# MCU_USB.net
KiCad netlist of a schematic drawn in Altium Designer
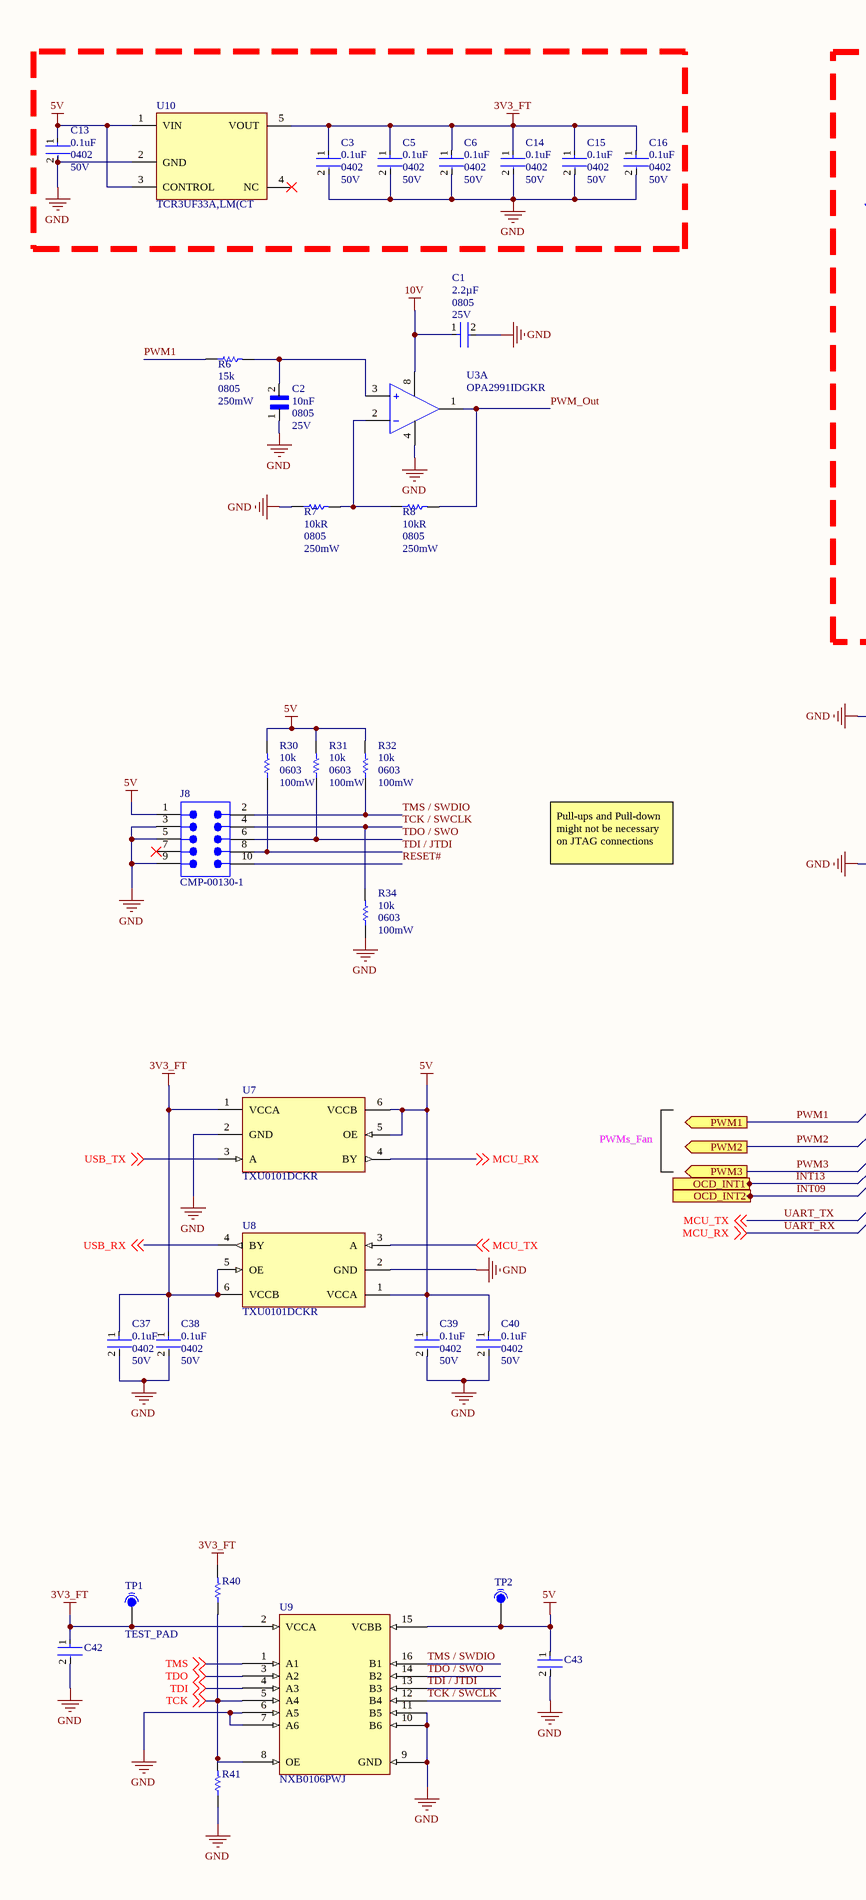
[diagram p0: MCU_USB.SchDoc, left]
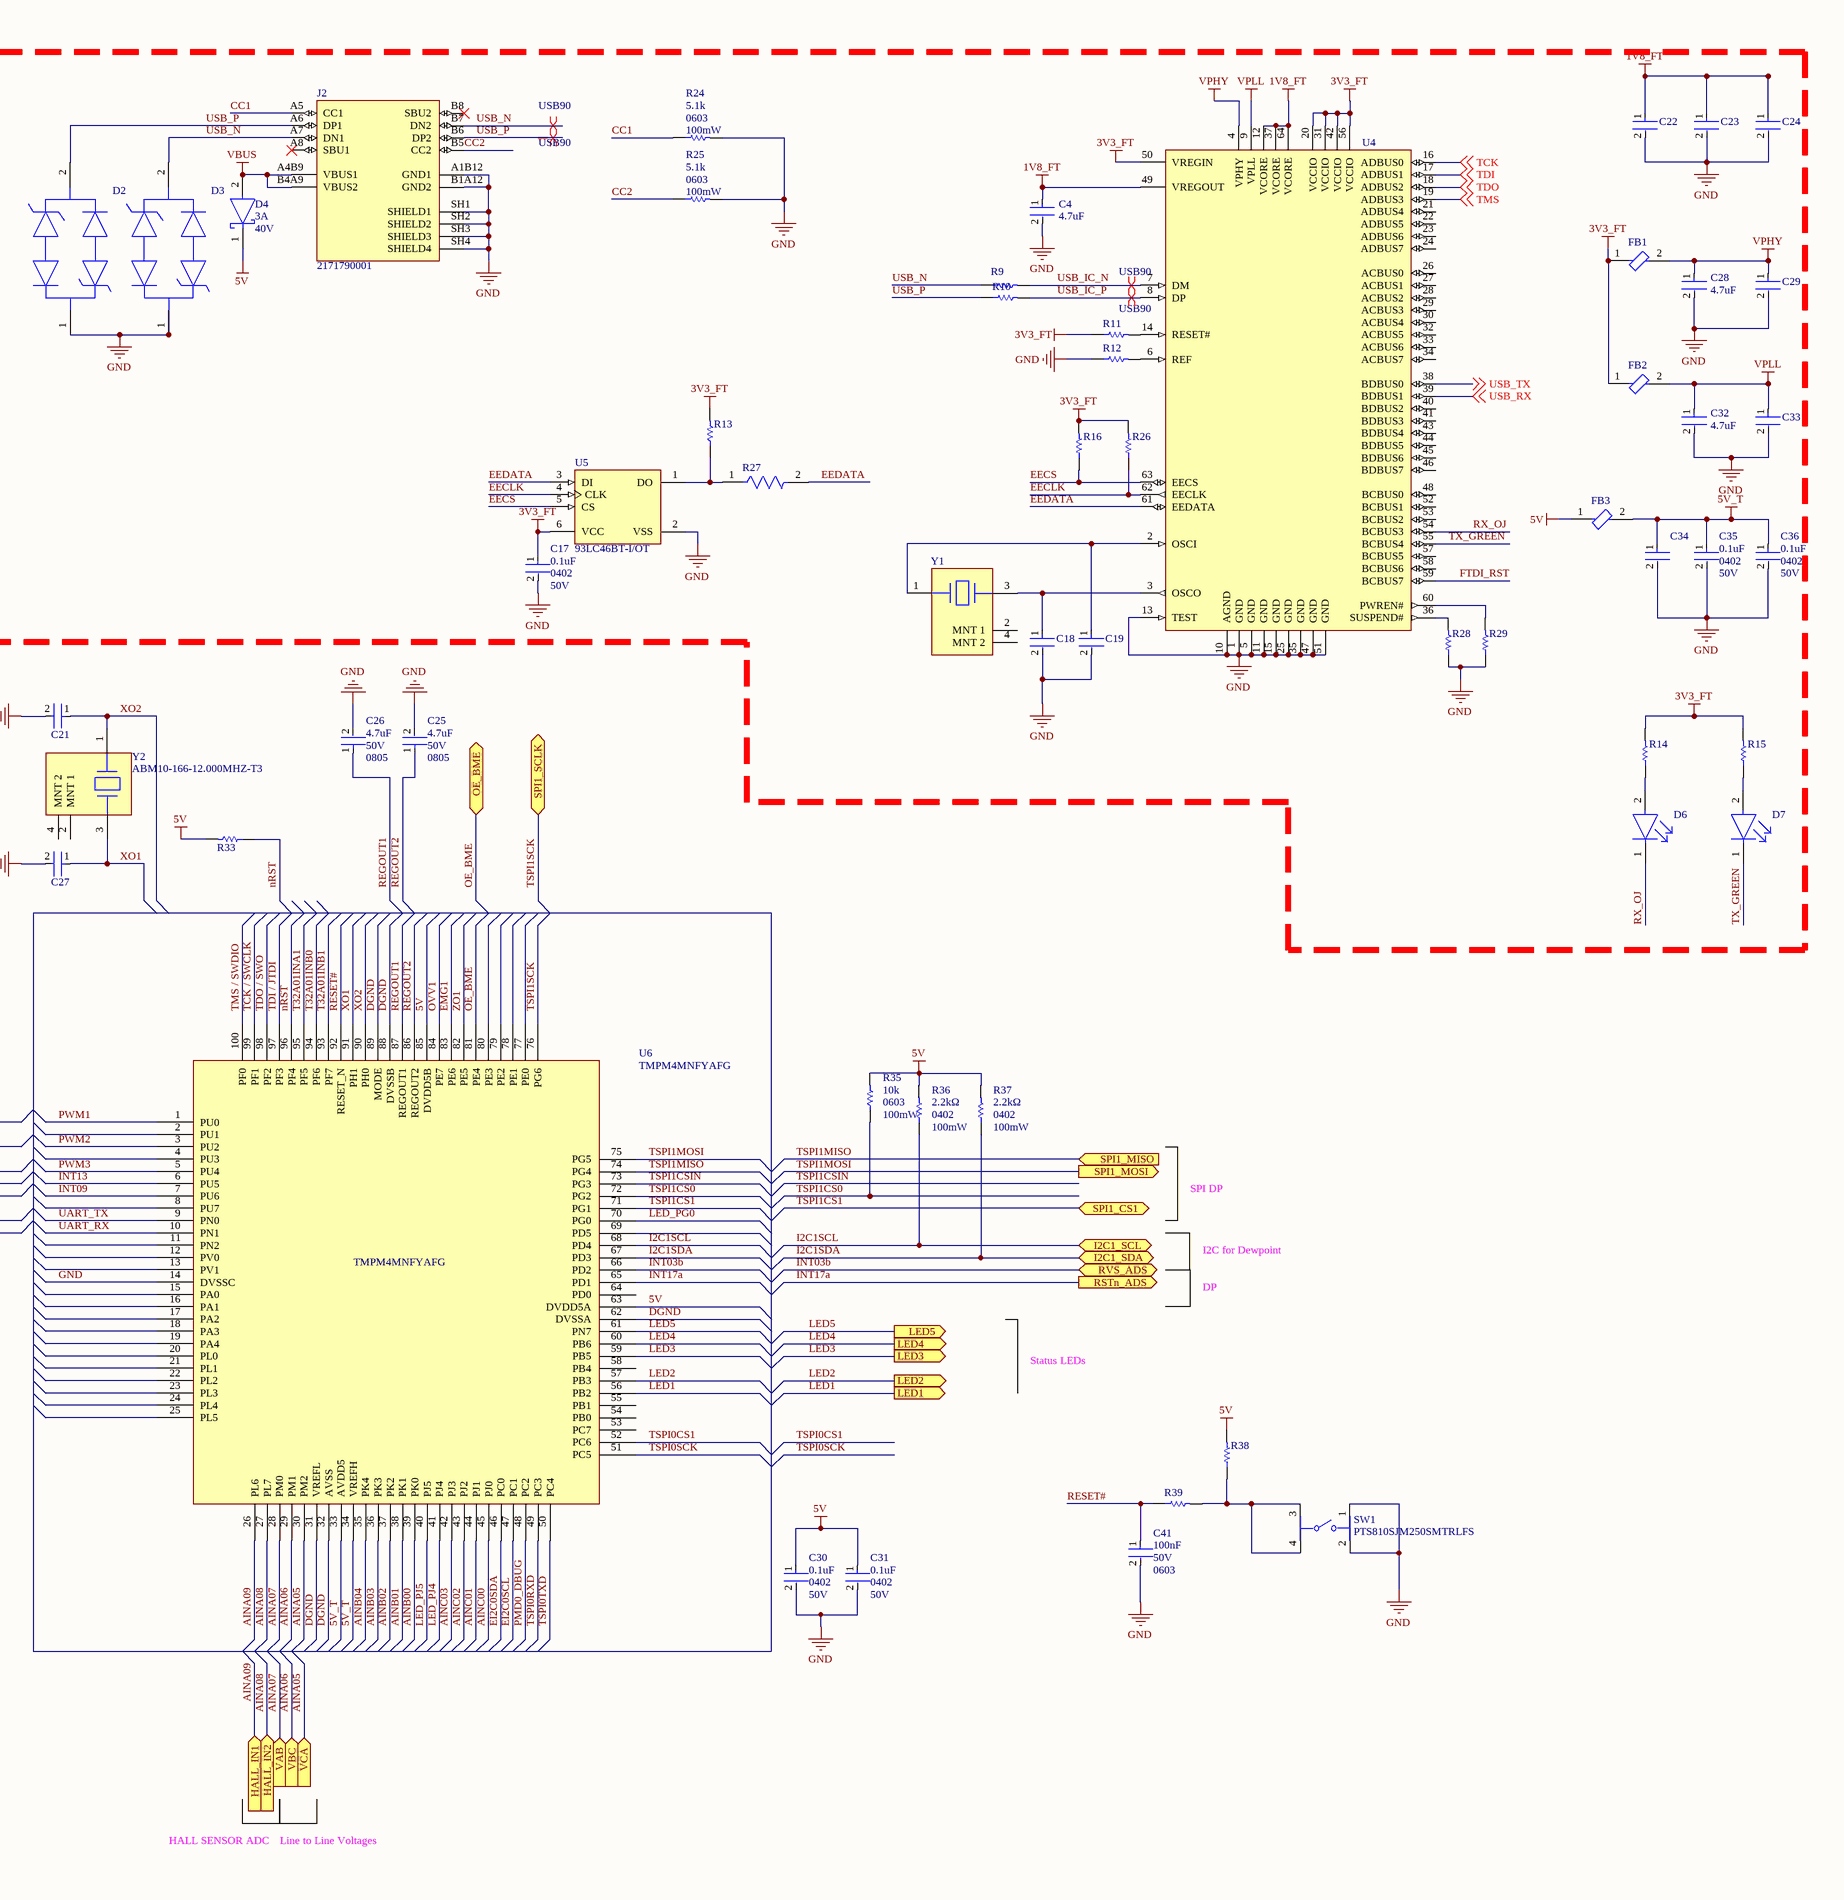
[diagram p1: MCU_USB.SchDoc, right]

(export (version "E")
  (design (tool "Eeschema 10.0.6"))
  (components
    (comp (ref "C1")
      (value "2.2µF")
      (footprint "FP-0805-L_2_01_0_2-W_1_25-IPC_A")
      (fields
        (field (name "CASE/PACKAGE") "0805")
        (field (name "VOLTAGE RATING") "25V")
        (field (name "Comment") "08053C225KAT2A")
      )
      (libsource (lib "Digital Shovel") (part "02cd4be3c70576c341d710602a673aa"))
    )
    (comp (ref "C2")
      (value "10nF")
      (footprint "C0805C103J3GECAUTO-Footprint-1")
      (fields
        (field (name "CASE/PACKAGE") "0805")
        (field (name "VOLTAGE RATING") "25V")
        (field (name "Comment") "C0805C103J3GECAUTO")
      )
      (libsource (lib "Digital Shovel") (part "C0805C103J3GECAUTO"))
    )
    (comp (ref "C3")
      (value "0.1uF")
      (footprint "FP-CGA2B-MFG")
      (description "Multilayer Ceramic Capacitor, 0.1 uF, 50 V, ± 10%, X7R, 0402 [1005 Metric]")
      (fields
        (field (name "RATING") "50V")
        (field (name "PACKAGE") "0402")
        (field (name "Comment") "CGA2B3X7R1H104K050BB")
      )
      (libsource (lib "Digital Shovel") (part "b4654b650e69147ec39a6b967a45e02"))
    )
    (comp (ref "C4")
      (value "GRM21BR61H475KE51L")
      (footprint "FP-GRM21B-0_15-IPC_B")
      (description "Chip Multilayer Ceramic Capacitors for General Purpose, 0805, 4.7uF, X5R, 15%, 10%, 50V")
      (fields (field (name "CAPACITANCE") "4.7uF") (field (name "TOLERANCE") "10%"))
      (libsource (lib "Altium Content Vault") (part "b4654b650e69147ec39a6b967a45e02"))
    )
    (comp (ref "C5")
      (value "0.1uF")
      (footprint "FP-CGA2B-MFG")
      (description "Multilayer Ceramic Capacitor, 0.1 uF, 50 V, ± 10%, X7R, 0402 [1005 Metric]")
      (fields
        (field (name "RATING") "50V")
        (field (name "PACKAGE") "0402")
        (field (name "Comment") "CGA2B3X7R1H104K050BB")
      )
      (libsource (lib "Digital Shovel") (part "b4654b650e69147ec39a6b967a45e02"))
    )
    (comp (ref "C6")
      (value "0.1uF")
      (footprint "FP-CGA2B-MFG")
      (description "Multilayer Ceramic Capacitor, 0.1 uF, 50 V, ± 10%, X7R, 0402 [1005 Metric]")
      (fields
        (field (name "RATING") "50V")
        (field (name "PACKAGE") "0402")
        (field (name "Comment") "CGA2B3X7R1H104K050BB")
      )
      (libsource (lib "Digital Shovel") (part "b4654b650e69147ec39a6b967a45e02"))
    )
    (comp (ref "C13")
      (value "0.1uF")
      (footprint "FP-CGA2B-MFG")
      (description "Multilayer Ceramic Capacitor, 0.1 uF, 50 V, ± 10%, X7R, 0402 [1005 Metric]")
      (fields
        (field (name "RATING") "50V")
        (field (name "PACKAGE") "0402")
        (field (name "Comment") "CGA2B3X7R1H104K050BB")
      )
      (libsource (lib "Digital Shovel") (part "b4654b650e69147ec39a6b967a45e02"))
    )
    (comp (ref "C14")
      (value "0.1uF")
      (footprint "FP-CGA2B-MFG")
      (description "Multilayer Ceramic Capacitor, 0.1 uF, 50 V, ± 10%, X7R, 0402 [1005 Metric]")
      (fields
        (field (name "RATING") "50V")
        (field (name "PACKAGE") "0402")
        (field (name "Comment") "CGA2B3X7R1H104K050BB")
      )
      (libsource (lib "Digital Shovel") (part "b4654b650e69147ec39a6b967a45e02"))
    )
    (comp (ref "C15")
      (value "0.1uF")
      (footprint "FP-CGA2B-MFG")
      (description "Multilayer Ceramic Capacitor, 0.1 uF, 50 V, ± 10%, X7R, 0402 [1005 Metric]")
      (fields
        (field (name "RATING") "50V")
        (field (name "PACKAGE") "0402")
        (field (name "Comment") "CGA2B3X7R1H104K050BB")
      )
      (libsource (lib "Digital Shovel") (part "b4654b650e69147ec39a6b967a45e02"))
    )
    (comp (ref "C16")
      (value "0.1uF")
      (footprint "FP-CGA2B-MFG")
      (description "Multilayer Ceramic Capacitor, 0.1 uF, 50 V, ± 10%, X7R, 0402 [1005 Metric]")
      (fields
        (field (name "RATING") "50V")
        (field (name "PACKAGE") "0402")
        (field (name "Comment") "CGA2B3X7R1H104K050BB")
      )
      (libsource (lib "Digital Shovel") (part "b4654b650e69147ec39a6b967a45e02"))
    )
    (comp (ref "C17")
      (value "0.1uF")
      (footprint "FP-CGA2B-MFG")
      (description "Multilayer Ceramic Capacitor, 0.1 uF, 50 V, ± 10%, X7R, 0402 [1005 Metric]")
      (fields
        (field (name "RATING") "50V")
        (field (name "PACKAGE") "0402")
        (field (name "Comment") "CGA2B3X7R1H104K050BB")
      )
      (libsource (lib "Digital Shovel") (part "b4654b650e69147ec39a6b967a45e02"))
    )
    (comp (ref "C18")
      (value "CBR08C809CAGAC")
      (footprint "FP-CBR08C-MFG")
      (description "CAP CER 8PF 250V C0G/NP0 0805")
      (fields
        (field (name "OCTOPART") "https://octopart.com/cbr08c809cagac-kemet-23841681")
        (field (name "TOLERANCE") "0.25 pF")
      )
      (libsource (lib "Altium Content Vault") (part "11868f565c42a9108669ba33697ecf6"))
    )
    (comp (ref "C19")
      (value "CBR08C809CAGAC")
      (footprint "FP-CBR08C-MFG")
      (description "CAP CER 8PF 250V C0G/NP0 0805")
      (fields
        (field (name "OCTOPART") "https://octopart.com/cbr08c809cagac-kemet-23841681")
        (field (name "TOLERANCE") "0.25 pF")
      )
      (libsource (lib "Altium Content Vault") (part "11868f565c42a9108669ba33697ecf6"))
    )
    (comp (ref "C21")
      (value "C0805C180K5GACTU")
      (footprint "FP-C0805C-DN-MFG")
      (description "CAP CER 18PF 50V 10% NP0 0805")
      (fields
        (field (name "OCTOPART") "https://octopart.com/c0805c180k5gactu-kemet-6728804")
        (field (name "MANUFACTURER") "KEMET")
      )
      (libsource (lib "Altium Content Vault") (part "b4654b650e69147ec39a6b967a45e02"))
    )
    (comp (ref "C22")
      (value "08055C104KAT2A")
      (footprint "FP-0805-L_2_01_0_2-W_1_25-IPC_C")
      (description "General Purpose Ceramic Capacitor, 0805, 100nF, 10%, X7R, 0.15, 50V")
      (fields (field (name "TOLERANCE") "10%") (field (name "VOLTAGE") "50V"))
      (libsource (lib "Altium Content Vault") (part "02cd4be3c70576c341d710602a673aa"))
    )
    (comp (ref "C23")
      (value "08055C104KAT2A")
      (footprint "FP-0805-L_2_01_0_2-W_1_25-IPC_C")
      (description "General Purpose Ceramic Capacitor, 0805, 100nF, 10%, X7R, 0.15, 50V")
      (fields (field (name "TOLERANCE") "10%") (field (name "VOLTAGE") "50V"))
      (libsource (lib "Altium Content Vault") (part "02cd4be3c70576c341d710602a673aa"))
    )
    (comp (ref "C24")
      (value "08055C104KAT2A")
      (footprint "FP-0805-L_2_01_0_2-W_1_25-IPC_C")
      (description "General Purpose Ceramic Capacitor, 0805, 100nF, 10%, X7R, 0.15, 50V")
      (fields (field (name "TOLERANCE") "10%") (field (name "VOLTAGE") "50V"))
      (libsource (lib "Altium Content Vault") (part "02cd4be3c70576c341d710602a673aa"))
    )
    (comp (ref "C25")
      (value "GRM21BR61H475KE51L")
      (footprint "FP-GRM21B-0_15-IPC_B")
      (description "Chip Multilayer Ceramic Capacitors for General Purpose, 0805, 4.7uF, X5R, 15%, 10%, 50V")
      (fields
        (field (name "CASE/PACKAGE") "0805")
        (field (name "CAPACITANCE") "4.7uF")
        (field (name "VOLTAGE RATING") "50V")
        (field (name "TOLERANCE") "10%")
      )
      (libsource (lib "Altium Content Vault") (part "b4654b650e69147ec39a6b967a45e02"))
    )
    (comp (ref "C26")
      (value "GRM21BR61H475KE51L")
      (footprint "FP-GRM21B-0_15-IPC_B")
      (description "Chip Multilayer Ceramic Capacitors for General Purpose, 0805, 4.7uF, X5R, 15%, 10%, 50V")
      (fields
        (field (name "CASE/PACKAGE") "0805")
        (field (name "CAPACITANCE") "4.7uF")
        (field (name "VOLTAGE RATING") "50V")
        (field (name "TOLERANCE") "10%")
      )
      (libsource (lib "Altium Content Vault") (part "b4654b650e69147ec39a6b967a45e02"))
    )
    (comp (ref "C27")
      (value "C0805C180K5GACTU")
      (footprint "FP-C0805C-DN-MFG")
      (description "CAP CER 18PF 50V 10% NP0 0805")
      (fields
        (field (name "OCTOPART") "https://octopart.com/c0805c180k5gactu-kemet-6728804")
        (field (name "MANUFACTURER") "KEMET")
      )
      (libsource (lib "Altium Content Vault") (part "b4654b650e69147ec39a6b967a45e02"))
    )
    (comp (ref "C28")
      (value "GRM21BR61H475KE51L")
      (footprint "FP-GRM21B-0_15-IPC_B")
      (description "Chip Multilayer Ceramic Capacitors for General Purpose, 0805, 4.7uF, X5R, 15%, 10%, 50V")
      (fields (field (name "CAPACITANCE") "4.7uF") (field (name "TOLERANCE") "10%"))
      (libsource (lib "Altium Content Vault") (part "b4654b650e69147ec39a6b967a45e02"))
    )
    (comp (ref "C29")
      (value "08055C104KAT2A")
      (footprint "FP-0805-L_2_01_0_2-W_1_25-IPC_C")
      (description "General Purpose Ceramic Capacitor, 0805, 100nF, 10%, X7R, 0.15, 50V")
      (fields (field (name "TOLERANCE") "10%") (field (name "VOLTAGE") "50V"))
      (libsource (lib "Altium Content Vault") (part "02cd4be3c70576c341d710602a673aa"))
    )
    (comp (ref "C30")
      (value "0.1uF")
      (footprint "FP-CGA2B-MFG")
      (description "Multilayer Ceramic Capacitor, 0.1 uF, 50 V, ± 10%, X7R, 0402 [1005 Metric]")
      (fields
        (field (name "RATING") "50V")
        (field (name "PACKAGE") "0402")
        (field (name "Comment") "CGA2B3X7R1H104K050BB")
      )
      (libsource (lib "Digital Shovel") (part "b4654b650e69147ec39a6b967a45e02"))
    )
    (comp (ref "C31")
      (value "0.1uF")
      (footprint "FP-CGA2B-MFG")
      (description "Multilayer Ceramic Capacitor, 0.1 uF, 50 V, ± 10%, X7R, 0402 [1005 Metric]")
      (fields
        (field (name "RATING") "50V")
        (field (name "PACKAGE") "0402")
        (field (name "Comment") "CGA2B3X7R1H104K050BB")
      )
      (libsource (lib "Digital Shovel") (part "b4654b650e69147ec39a6b967a45e02"))
    )
    (comp (ref "C32")
      (value "GRM21BR61H475KE51L")
      (footprint "FP-GRM21B-0_15-IPC_B")
      (description "Chip Multilayer Ceramic Capacitors for General Purpose, 0805, 4.7uF, X5R, 15%, 10%, 50V")
      (fields (field (name "CAPACITANCE") "4.7uF") (field (name "TOLERANCE") "10%"))
      (libsource (lib "Altium Content Vault") (part "b4654b650e69147ec39a6b967a45e02"))
    )
    (comp (ref "C33")
      (value "08055C104KAT2A")
      (footprint "FP-0805-L_2_01_0_2-W_1_25-IPC_C")
      (description "General Purpose Ceramic Capacitor, 0805, 100nF, 10%, X7R, 0.15, 50V")
      (fields (field (name "TOLERANCE") "10%") (field (name "VOLTAGE") "50V"))
      (libsource (lib "Altium Content Vault") (part "02cd4be3c70576c341d710602a673aa"))
    )
    (comp (ref "C34")
      (value "GRM21BR61C106KE15K")
      (footprint "FP-GRM21B-0_1-MFG")
      (description "Chip Multilayer Ceramic Capacitors for General Purpose, 0805, 10uF, X5R, 15%, 10%, 16V")
      (fields (field (name "TOLERANCE") "10%") (field (name "VOLTAGE") "16V"))
      (libsource (lib "Altium Content Vault") (part "b4654b650e69147ec39a6b967a45e02"))
    )
    (comp (ref "C35")
      (value "0.1uF")
      (footprint "FP-CGA2B-MFG")
      (description "Multilayer Ceramic Capacitor, 0.1 uF, 50 V, ± 10%, X7R, 0402 [1005 Metric]")
      (fields
        (field (name "RATING") "50V")
        (field (name "PACKAGE") "0402")
        (field (name "Comment") "CGA2B3X7R1H104K050BB")
      )
      (libsource (lib "Digital Shovel") (part "b4654b650e69147ec39a6b967a45e02"))
    )
    (comp (ref "C36")
      (value "0.1uF")
      (footprint "FP-CGA2B-MFG")
      (description "Multilayer Ceramic Capacitor, 0.1 uF, 50 V, ± 10%, X7R, 0402 [1005 Metric]")
      (fields
        (field (name "RATING") "50V")
        (field (name "PACKAGE") "0402")
        (field (name "Comment") "CGA2B3X7R1H104K050BB")
      )
      (libsource (lib "Digital Shovel") (part "b4654b650e69147ec39a6b967a45e02"))
    )
    (comp (ref "C37")
      (value "0.1uF")
      (footprint "FP-CGA2B-MFG")
      (description "Multilayer Ceramic Capacitor, 0.1 uF, 50 V, ± 10%, X7R, 0402 [1005 Metric]")
      (fields
        (field (name "RATING") "50V")
        (field (name "PACKAGE") "0402")
        (field (name "Comment") "CGA2B3X7R1H104K050BB")
      )
      (libsource (lib "Digital Shovel") (part "b4654b650e69147ec39a6b967a45e02"))
    )
    (comp (ref "C38")
      (value "0.1uF")
      (footprint "FP-CGA2B-MFG")
      (description "Multilayer Ceramic Capacitor, 0.1 uF, 50 V, ± 10%, X7R, 0402 [1005 Metric]")
      (fields
        (field (name "RATING") "50V")
        (field (name "PACKAGE") "0402")
        (field (name "Comment") "CGA2B3X7R1H104K050BB")
      )
      (libsource (lib "Digital Shovel") (part "b4654b650e69147ec39a6b967a45e02"))
    )
    (comp (ref "C39")
      (value "0.1uF")
      (footprint "FP-CGA2B-MFG")
      (description "Multilayer Ceramic Capacitor, 0.1 uF, 50 V, ± 10%, X7R, 0402 [1005 Metric]")
      (fields
        (field (name "RATING") "50V")
        (field (name "PACKAGE") "0402")
        (field (name "Comment") "CGA2B3X7R1H104K050BB")
      )
      (libsource (lib "Digital Shovel") (part "b4654b650e69147ec39a6b967a45e02"))
    )
    (comp (ref "C40")
      (value "0.1uF")
      (footprint "FP-CGA2B-MFG")
      (description "Multilayer Ceramic Capacitor, 0.1 uF, 50 V, ± 10%, X7R, 0402 [1005 Metric]")
      (fields
        (field (name "RATING") "50V")
        (field (name "PACKAGE") "0402")
        (field (name "Comment") "CGA2B3X7R1H104K050BB")
      )
      (libsource (lib "Digital Shovel") (part "b4654b650e69147ec39a6b967a45e02"))
    )
    (comp (ref "C41")
      (value "100nF")
      (footprint "FP-C0603C-CF-IPC_A")
      (fields
        (field (name "VOLTAGE RATING") "50V")
        (field (name "CASE/PACKAGE") "0603")
        (field (name "Comment") "C0603C104K5RACTU")
      )
      (libsource (lib "Digital Shovel") (part "b4654b650e69147ec39a6b967a45e02"))
    )
    (comp (ref "C42")
      (value "08055C104KAT2A")
      (footprint "FP-0805-L_2_01_0_2-W_1_25-IPC_C")
      (description "General Purpose Ceramic Capacitor, 0805, 100nF, 10%, X7R, 0.15, 50V")
      (fields (field (name "TOLERANCE") "10%") (field (name "VOLTAGE") "50V"))
      (libsource (lib "Altium Content Vault") (part "02cd4be3c70576c341d710602a673aa"))
    )
    (comp (ref "C43")
      (value "08055C104KAT2A")
      (footprint "FP-0805-L_2_01_0_2-W_1_25-IPC_C")
      (description "General Purpose Ceramic Capacitor, 0805, 100nF, 10%, X7R, 0.15, 50V")
      (fields (field (name "TOLERANCE") "10%") (field (name "VOLTAGE") "50V"))
      (libsource (lib "Altium Content Vault") (part "02cd4be3c70576c341d710602a673aa"))
    )
    (comp (ref "D2")
      (value "CDSOD323-T05C")
      (footprint "FP-SOD-323-IPC_A")
      (description "Trans Voltage Suppressor Diode, 350W, 5V V(RWM), Bidirectional, 2 Element, Silicon")
      (libsource (lib "Digital Shovel") (part "779a55c44692ffd9a70040819656d00"))
    )
    (comp (ref "D3")
      (value "CDSOD323-T05C")
      (footprint "FP-SOD-323-IPC_A")
      (description "Trans Voltage Suppressor Diode, 350W, 5V V(RWM), Bidirectional, 2 Element, Silicon")
      (libsource (lib "Digital Shovel") (part "779a55c44692ffd9a70040819656d00"))
    )
    (comp (ref "D4")
      (value "3A")
      (footprint "FP-SOD123W-MFG")
      (description "Rectifier Diode, Schottky, 1 Phase, 1 Element, 3A, 40V V(RRM), Silicon")
      (fields
        (field (name "MANUFACTURER") "Nexperia")
        (field (name "VOLTAGE RATING") "40V")
        (field (name "Comment") "PMEG4030ER,115")
      )
      (libsource (lib "Digital Shovel") (part "e9b750318ede8d9850c058872da20e7"))
    )
    (comp (ref "D6")
      (value "APT3216LSECK/J4-PRV")
      (footprint "FP-APT3216LSECK-J4-PRV-MFG")
      (description "LED ORANGE CLEAR 2SMD")
      (libsource (lib "Altium Content Vault") (part "8706943c75ba83719d021d2fdc84c58"))
    )
    (comp (ref "D7")
      (value "APT3216LZGCK")
      (footprint "FP-APT3216LSECK-J4-PRV-MFG")
      (description "LED ORANGE CLEAR 2SMD")
      (libsource (lib "Altium Content Vault") (part "8706943c75ba83719d021d2fdc84c58"))
    )
    (comp (ref "FB1")
      (value "BLM21PG300SN1D")
      (footprint "FP-BLM21-0_2-t0_85-e0_5-d-MFG")
      (description "Chip Ferrite Bead, 0805, 30Ω @ 100MHz, 0.014Ω, , 4A")
      (fields (field (name "TOLERANCE") "25%"))
      (libsource (lib "Altium Content Vault") (part "5f30dd21d616792df468990f7003faa"))
    )
    (comp (ref "FB2")
      (value "BLM21PG300SN1D")
      (footprint "FP-BLM21-0_2-t0_85-e0_5-d-MFG")
      (description "Chip Ferrite Bead, 0805, 30Ω @ 100MHz, 0.014Ω, , 4A")
      (fields (field (name "TOLERANCE") "25%"))
      (libsource (lib "Altium Content Vault") (part "5f30dd21d616792df468990f7003faa"))
    )
    (comp (ref "FB3")
      (value "MPZ2012S221AT000")
      (footprint "FP-MPZ2012-MFG")
      (description "FERRITE BEAD 220 OHM 0805 1LN")
      (fields (field (name "TOLERANCE") "25%"))
      (libsource (lib "Altium Content Vault") (part "5f30dd21d616792df468990f7003faa"))
    )
    (comp (ref "J2")
      (value "2171790001")
      (footprint "2171790001-Footprint-1")
      (description "Top-mount SMT 16pos (Type C")
      (fields (field (name "MANUFACTURER") "MOLEX"))
      (libsource (lib "Digital Shovel") (part "2171790001-Symbol-1"))
    )
    (comp (ref "J8")
      (value "CMP-00130-1")
      (footprint "FP-M50-3600542R-MFG")
      (libsource (lib "Digital Shovel") (part "CMP-00130-1"))
    )
    (comp (ref "R6")
      (value "15k")
      (footprint "RESC2013X60X30ML20T20")
      (fields
        (field (name "TOLERANCE") "1%")
        (field (name "CASE/PACKAGE") "0805")
        (field (name "POWER") "250mW")
        (field (name "Comment") "RK73H2ATTD1502F")
      )
      (libsource (lib "Digital Shovel") (part "RES"))
    )
    (comp (ref "R7")
      (value "10kR")
      (footprint "RESC2013X60X30ML20T20")
      (description "Resistor Thick Film 0805 10K Ohm 1% 1/8W ±100ppm/°C SMD Punched Paper Tape and Reel")
      (fields
        (field (name "MAX POWER DISSIPATION") "250mW")
        (field (name "CASE CODE (IMPERIAL)") "0805")
        (field (name "TOLERANCE") "1%")
        (field (name "Comment") "RK73H2ATTD1002F")
      )
      (libsource (lib "Digital Shovel") (part "RES"))
    )
    (comp (ref "R8")
      (value "10kR")
      (footprint "RESC2013X60X30ML20T20")
      (description "Resistor Thick Film 0805 10K Ohm 1% 1/8W ±100ppm/°C SMD Punched Paper Tape and Reel")
      (fields
        (field (name "MAX POWER DISSIPATION") "250mW")
        (field (name "CASE CODE (IMPERIAL)") "0805")
        (field (name "TOLERANCE") "1%")
        (field (name "Comment") "RK73H2ATTD1002F")
      )
      (libsource (lib "Digital Shovel") (part "RES"))
    )
    (comp (ref "R9")
      (value "RK73B2ATTD270J")
      (footprint "RESC2013X60X30ML20T20")
      (fields (field (name "MANUFACTURER") "KOA Speer"))
      (libsource (lib "Altium Content Vault") (part "RES"))
    )
    (comp (ref "R10")
      (value "RK73B2ATTD270J")
      (footprint "RESC2013X60X30ML20T20")
      (fields (field (name "MANUFACTURER") "KOA Speer"))
      (libsource (lib "Altium Content Vault") (part "RES"))
    )
    (comp (ref "R11")
      (value "RC0805FR-071KL")
      (footprint "RESC2013X60X35ML10T20")
      (description "Chip Resistor, 1 KOhm, +/- 1%, 125 mW, -55 to 155 degC, 0805 (2012 Metric), RoHS, Tape and Reel")
      (fields (field (name "TOLERANCE") "1%") (field (name "MANUFACTURER") "Yageo"))
      (libsource (lib "Altium Content Vault") (part "RES-2"))
    )
    (comp (ref "R12")
      (value "ERJ-6GEYJ123V")
      (footprint "RESC2013X70X40ML20T20")
      (fields (field (name "MANUFACTURER") "Panasonic"))
      (libsource (lib "Altium Content Vault") (part "RES"))
    )
    (comp (ref "R13")
      (value "RK73H2ATTD1002F")
      (footprint "RESC2013X60X30LL20T20")
      (fields (field (name "MANUFACTURER") "KOA Speer"))
      (libsource (lib "Altium Content Vault") (part "RES"))
    )
    (comp (ref "R14")
      (value "RC0805FR-071KL")
      (footprint "RESC2013X60X35ML10T20")
      (description "Chip Resistor, 1 KOhm, +/- 1%, 125 mW, -55 to 155 degC, 0805 (2012 Metric), RoHS, Tape and Reel")
      (fields (field (name "TOLERANCE") "1%") (field (name "MANUFACTURER") "Yageo"))
      (libsource (lib "Altium Content Vault") (part "RES-2"))
    )
    (comp (ref "R15")
      (value "RC0805FR-071KL")
      (footprint "RESC2013X60X35ML10T20")
      (description "Chip Resistor, 1 KOhm, +/- 1%, 125 mW, -55 to 155 degC, 0805 (2012 Metric), RoHS, Tape and Reel")
      (fields (field (name "TOLERANCE") "1%") (field (name "MANUFACTURER") "Yageo"))
      (libsource (lib "Altium Content Vault") (part "RES-2"))
    )
    (comp (ref "R16")
      (value "RK73H2ATTD1002F")
      (footprint "RESC2013X60X30LL20T20")
      (fields (field (name "MANUFACTURER") "KOA Speer"))
      (libsource (lib "Altium Content Vault") (part "RES"))
    )
    (comp (ref "R24")
      (value "5.1k")
      (footprint "RESC1608X55X30LL20T10")
      (fields
        (field (name "CASE/PACKAGE") "0603")
        (field (name "POWER") "100mW")
        (field (name "TOLERANCE") "1%")
        (field (name "Comment") "RK73H1JTTD5101F")
      )
      (libsource (lib "Digital Shovel") (part "RES"))
    )
    (comp (ref "R25")
      (value "5.1k")
      (footprint "RESC1608X55X30LL20T10")
      (fields
        (field (name "CASE/PACKAGE") "0603")
        (field (name "POWER") "100mW")
        (field (name "TOLERANCE") "1%")
        (field (name "Comment") "RK73H1JTTD5101F")
      )
      (libsource (lib "Digital Shovel") (part "RES"))
    )
    (comp (ref "R26")
      (value "RK73H2ATTD1002F")
      (footprint "RESC2013X60X30LL20T20")
      (fields (field (name "MANUFACTURER") "KOA Speer"))
      (libsource (lib "Altium Content Vault") (part "RES"))
    )
    (comp (ref "R27")
      (value "RMCF0805JT2K20")
      (footprint "FP-RMCF0805-IPC_C")
      (description "2.2kΩ ±5% 0.125W 0805 Thick Film Chip Resistor AEC-Q200 compliant")
      (fields (field (name "TOLERANCE") "5%"))
      (libsource (lib "Altium Content Vault") (part "1029c3af85768c4190bb7ad29bc67b5"))
    )
    (comp (ref "R28")
      (value "ERJ-6GEY0R00V")
      (footprint "RESC2013X70X40NL20T20")
      (description "Chip Resistor, 0 Ohm, +/- 1%, 0.125 W, -55 to 155 degC, 0805 (2012 Metric), RoHS, Tape and Reel")
      (fields (field (name "TOLERANCE") "5%"))
      (libsource (lib "Altium Content Vault") (part "RES-2"))
    )
    (comp (ref "R29")
      (value "ERJ-6GEY0R00V")
      (footprint "RESC2013X70X40NL20T20")
      (description "Chip Resistor, 0 Ohm, +/- 1%, 0.125 W, -55 to 155 degC, 0805 (2012 Metric), RoHS, Tape and Reel")
      (fields (field (name "TOLERANCE") "5%"))
      (libsource (lib "Altium Content Vault") (part "RES-2"))
    )
    (comp (ref "R30")
      (value "10k")
      (footprint "RESC1608X55X30LL20T10")
      (fields
        (field (name "TOLERANCE") "1%")
        (field (name "POWER") "100mW")
        (field (name "CASE/PACKAGE") "0603")
        (field (name "Comment") "RK73H1JTTD1002F")
      )
      (libsource (lib "Digital Shovel") (part "RES"))
    )
    (comp (ref "R31")
      (value "10k")
      (footprint "RESC1608X55X30LL20T10")
      (fields
        (field (name "TOLERANCE") "1%")
        (field (name "POWER") "100mW")
        (field (name "CASE/PACKAGE") "0603")
        (field (name "Comment") "RK73H1JTTD1002F")
      )
      (libsource (lib "Digital Shovel") (part "RES"))
    )
    (comp (ref "R32")
      (value "10k")
      (footprint "RESC1608X55X30LL20T10")
      (fields
        (field (name "TOLERANCE") "1%")
        (field (name "POWER") "100mW")
        (field (name "CASE/PACKAGE") "0603")
        (field (name "Comment") "RK73H1JTTD1002F")
      )
      (libsource (lib "Digital Shovel") (part "RES"))
    )
    (comp (ref "R33")
      (value "ERJ-6GEY0R00V")
      (footprint "RESC2013X70X40NL20T20")
      (description "Chip Resistor, 0 Ohm, +/- 1%, 0.125 W, -55 to 155 degC, 0805 (2012 Metric), RoHS, Tape and Reel")
      (fields (field (name "TOLERANCE") "5%"))
      (libsource (lib "Altium Content Vault") (part "RES-2"))
    )
    (comp (ref "R34")
      (value "10k")
      (footprint "RESC1608X55X30LL20T10")
      (fields
        (field (name "TOLERANCE") "1%")
        (field (name "POWER") "100mW")
        (field (name "CASE/PACKAGE") "0603")
        (field (name "Comment") "RK73H1JTTD1002F")
      )
      (libsource (lib "Digital Shovel") (part "RES"))
    )
    (comp (ref "R35")
      (value "10k")
      (footprint "RESC1608X55X30LL20T10")
      (fields
        (field (name "TOLERANCE") "1%")
        (field (name "POWER") "100mW")
        (field (name "CASE/PACKAGE") "0603")
        (field (name "Comment") "RK73H1JTTD1002F")
      )
      (libsource (lib "Digital Shovel") (part "RES"))
    )
    (comp (ref "R36")
      (value "2.2kΩ")
      (footprint "RK73H1ETTP2201F-Footprint-1")
      (fields
        (field (name "PACKAGE") "0402")
        (field (name "RATING") "100mW")
        (field (name "MANUFACTURER") "KOA Speer")
        (field (name "Comment") "RK73H1ETTP2201F")
      )
      (libsource (lib "Digital Shovel") (part "RES"))
    )
    (comp (ref "R37")
      (value "2.2kΩ")
      (footprint "RK73H1ETTP2201F-Footprint-1")
      (fields
        (field (name "PACKAGE") "0402")
        (field (name "RATING") "100mW")
        (field (name "MANUFACTURER") "KOA Speer")
        (field (name "Comment") "RK73H1ETTP2201F")
      )
      (libsource (lib "Digital Shovel") (part "RES"))
    )
    (comp (ref "R38")
      (value "RK73H2ATTD1002F")
      (footprint "RESC2013X60X30LL20T20")
      (fields (field (name "MANUFACTURER") "KOA Speer"))
      (libsource (lib "Altium Content Vault") (part "RES"))
    )
    (comp (ref "R39")
      (value "ERJ-6GEYJ331V")
      (footprint "RESC2013X70X40ML20T20")
      (fields (field (name "MANUFACTURER") "Panasonic"))
      (libsource (lib "Altium Content Vault") (part "RES"))
    )
    (comp (ref "R40")
      (value "RK73H2ATTD1002F")
      (footprint "RESC2013X60X30LL20T20")
      (fields (field (name "MANUFACTURER") "KOA Speer"))
      (libsource (lib "Altium Content Vault") (part "RES"))
    )
    (comp (ref "R41")
      (value "ERJ-6GEY0R00V")
      (footprint "RESC2013X70X40NL20T20")
      (description "Chip Resistor, 0 Ohm, +/- 1%, 0.125 W, -55 to 155 degC, 0805 (2012 Metric), RoHS, Tape and Reel")
      (fields (field (name "TOLERANCE") "5%"))
      (libsource (lib "Altium Content Vault") (part "RES-2"))
    )
    (comp (ref "SW1")
      (value "PTS810SJM250SMTRLFS")
      (footprint "FP-PTS810SJM250SMTRLFS-MFG")
      (fields (field (name "MANUFACTURER") "C&K"))
      (libsource (lib "Digital Shovel") (part "1adf0dd01260c80cf25a44bfd6b99ba"))
    )
    (comp (ref "TP1")
      (value "TEST_PAD")
      (footprint "TEST_PAD-Footprint-1")
      (description "For use with : 0978-0-15-20-75-14-11-0 MillMaxCorp")
      (libsource (lib "Digital Shovel") (part "TEST_PAD-Symbol-1"))
    )
    (comp (ref "TP2")
      (value "TEST_PAD")
      (footprint "TEST_PAD-Footprint-1")
      (description "For use with : 0978-0-15-20-75-14-11-0 MillMaxCorp")
      (libsource (lib "Digital Shovel") (part "TEST_PAD-Symbol-1"))
    )
    (comp (ref "U3")
      (value "OPA2991IDGKR")
      (footprint "FP-DGK0008A-IPC_B")
      (description "Operational Amplifier, 2 Func, 750uV Offset-Max, PDSO8")
      (fields (field (name "MANUFACTURER") "TI"))
      (libsource (lib "Digital Shovel") (part "4130030277608888969bec034a88852"))
    )
    (comp (ref "U4")
      (value "FT2232HL-REEL")
      (footprint "LQFP-64_M")
      (description "USB Bus Controller, CMOS, PQFP64")
      (fields (field (name "MANUFACTURER") "FTDI"))
      (libsource (lib "Digital Shovel") (part "COM-UART-FT2232H-LQFP64"))
    )
    (comp (ref "U5")
      (value "93LC46BT-I/OT")
      (footprint "SOT-23-OT6_M")
      (description "EEPROM, 64X16, Serial, CMOS, PDSO6")
      (fields (field (name "MANUFACTURER") "Microchip Technology"))
      (libsource (lib "Digital Shovel") (part "MEM-SEEPROM-93AA46B-OT-6"))
    )
    (comp (ref "U6")
      (value "TMPM4MNFYAFG")
      (footprint "TSQFP50P1600X1600X145-100N")
      (description "Toshiba Micro")
      (libsource (lib "Digital Shovel") (part "TMPM4MNFYAFG"))
    )
    (comp (ref "U7")
      (value "TXU0101DCKR")
      (footprint "FP-DCK0006A-MFG")
      (description "Single channel fixed-direction level shifter 6-SC70 -40 to 125")
      (libsource (lib "Digital Shovel") (part "TXU0101DCKR"))
    )
    (comp (ref "U8")
      (value "TXU0101DCKR")
      (footprint "FP-DCK0006A-MFG")
      (description "Single channel fixed-direction level shifter 6-SC70 -40 to 125")
      (libsource (lib "") (part "TXU0101DCKR_1"))
    )
    (comp (ref "U9")
      (value "NXB0106PWJ")
      (footprint "TSOP65P640X120-16N")
      (description "NXB0106 - Dual supply translating transceiver; auto direction sensing; 3-state")
      (libsource (lib "Digital Shovel") (part "NXB0106PWJ-Symbol-1"))
    )
    (comp (ref "U10")
      (value "TCR3UF33A,LM(CT")
      (footprint "TCR3UF33A,LM(CT-Footprint-1")
      (description "(ldo) Linear Voltage Reg, Vin: 6")
      (fields (field (name "MANUFACTURER") "Toshiba"))
      (libsource (lib "Digital Shovel") (part "TCR3UF33A,LM(CT-Symbol-1"))
    )
    (comp (ref "Y1")
      (value "ABM10-166-12.000MHZ-T3")
      (footprint "FP-ABM10-166-167-MFG")
      (description "Crystal 12MHz ±10ppm (Tol) ±10ppm (Stability) 8pF FUND 125Ohm 4-Pin SMD T/R")
      (fields (field (name "MANUFACTURER") "TI"))
      (libsource (lib "Digital Shovel") (part "c1e6c4da84e2560fa339d1e93faccc5"))
    )
    (comp (ref "Y2")
      (value "ABM10-166-12.000MHZ-T3")
      (footprint "FP-ABM10-166-167-MFG")
      (description "Crystal 12MHz ±10ppm (Tol) ±10ppm (Stability) 8pF FUND 125Ohm 4-Pin SMD T/R")
      (fields (field (name "MANUFACTURER") "TI"))
      (libsource (lib "") (part "c1e6c4da84e2560fa339d1e93faccc5_1"))
    )
  )
  (nets
    (net (code "1") (name "/AINA05") (class "Default")
      (node (ref "U6") (pin "30") (pinfunction "PM2_30") (pintype "passive"))
    )
    (net (code "2") (name "/AINA06") (class "Default")
      (node (ref "U6") (pin "29") (pinfunction "PM1_29") (pintype "passive"))
    )
    (net (code "3") (name "/AINA07") (class "Default")
      (node (ref "U6") (pin "28") (pinfunction "PM0_28") (pintype "passive"))
    )
    (net (code "4") (name "/AINA08") (class "Default")
      (node (ref "U6") (pin "27") (pinfunction "PL7_27") (pintype "passive"))
    )
    (net (code "5") (name "/AINA09") (class "Default")
      (node (ref "U6") (pin "26") (pinfunction "PL6_26") (pintype "passive"))
    )
    (net (code "6") (name "/AINB00") (class "Default")
      (node (ref "U6") (pin "39") (pinfunction "PK0_39") (pintype "passive"))
    )
    (net (code "7") (name "/AINB01") (class "Default")
      (node (ref "U6") (pin "38") (pinfunction "PK1_38") (pintype "passive"))
    )
    (net (code "8") (name "/AINB02") (class "Default")
      (node (ref "U6") (pin "37") (pinfunction "PK2_37") (pintype "passive"))
    )
    (net (code "9") (name "/AINB03") (class "Default")
      (node (ref "U6") (pin "36") (pinfunction "PK3_36") (pintype "passive"))
    )
    (net (code "10") (name "/AINB04") (class "Default")
      (node (ref "U6") (pin "35") (pinfunction "PK4_35") (pintype "passive"))
    )
    (net (code "11") (name "/AINC00") (class "Default")
      (node (ref "U6") (pin "45") (pinfunction "PJ0_45") (pintype "passive"))
    )
    (net (code "12") (name "/AINC01") (class "Default")
      (node (ref "U6") (pin "44") (pinfunction "PJ1_44") (pintype "passive"))
    )
    (net (code "13") (name "/AINC02") (class "Default")
      (node (ref "U6") (pin "43") (pinfunction "PJ2_43") (pintype "passive"))
    )
    (net (code "14") (name "/AINC03") (class "Default")
      (node (ref "U6") (pin "42") (pinfunction "PJ3_42") (pintype "passive"))
    )
    (net (code "15") (name "/CC1") (class "Default")
      (node (ref "J2") (pin "A5") (pinfunction "CC1_A5") (pintype "bidirectional"))
      (node (ref "R24") (pin "1") (pinfunction "1_1") (pintype "passive"))
    )
    (net (code "16") (name "/CC2") (class "Default")
      (node (ref "J2") (pin "B5") (pinfunction "CC2_B5") (pintype "bidirectional"))
      (node (ref "R25") (pin "1") (pinfunction "1_1") (pintype "passive"))
    )
    (net (code "17") (name "/DGND") (class "Default")
      (node (ref "U6") (pin "31") (pinfunction "VREFL_31") (pintype "passive"))
      (node (ref "U6") (pin "32") (pinfunction "AVSS_32") (pintype "passive"))
      (node (ref "U6") (pin "62") (pinfunction "DVSSA_62") (pintype "passive"))
      (node (ref "U6") (pin "88") (pinfunction "DVSSB_88") (pintype "passive"))
      (node (ref "U6") (pin "89") (pinfunction "MODE_89") (pintype "passive"))
    )
    (net (code "18") (name "/EECLK") (class "Default")
      (node (ref "R26") (pin "1") (pinfunction "1_1") (pintype "passive"))
      (node (ref "U4") (pin "62") (pinfunction "EECLK_62") (pintype "output"))
      (node (ref "U5") (pin "4") (pinfunction "CLK_4") (pintype "input"))
    )
    (net (code "19") (name "/EECS") (class "Default")
      (node (ref "R16") (pin "1") (pinfunction "1_1") (pintype "passive"))
      (node (ref "U4") (pin "63") (pinfunction "EECS_63") (pintype "bidirectional"))
      (node (ref "U5") (pin "5") (pinfunction "CS_5") (pintype "input"))
    )
    (net (code "20") (name "/EEDATA") (class "Default")
      (node (ref "R27") (pin "2") (pinfunction "2_2") (pintype "passive"))
      (node (ref "U4") (pin "61") (pinfunction "EEDATA_61") (pintype "bidirectional"))
      (node (ref "U5") (pin "3") (pinfunction "DI_3") (pintype "input"))
    )
    (net (code "21") (name "/EI2C0SCL") (class "Default")
      (node (ref "U6") (pin "47") (pinfunction "PC1_47") (pintype "passive"))
    )
    (net (code "22") (name "/EI2C0SDA") (class "Default")
      (node (ref "U6") (pin "46") (pinfunction "PC0_46") (pintype "passive"))
    )
    (net (code "23") (name "/EMG1") (class "Default")
      (node (ref "U6") (pin "83") (pinfunction "PE6_83") (pintype "passive"))
    )
    (net (code "24") (name "/FTDI_RST") (class "Default")
      (node (ref "U4") (pin "59") (pinfunction "BCBUS7_59") (pintype "bidirectional"))
    )
    (net (code "25") (name "/I2C1SCL") (class "Default")
      (node (ref "R36") (pin "1") (pinfunction "1_1") (pintype "passive"))
      (node (ref "U6") (pin "68") (pinfunction "PD4_68") (pintype "passive"))
    )
    (net (code "26") (name "/I2C1SDA") (class "Default")
      (node (ref "R37") (pin "1") (pinfunction "1_1") (pintype "passive"))
      (node (ref "U6") (pin "67") (pinfunction "PD3_67") (pintype "passive"))
    )
    (net (code "27") (name "/INT03b") (class "Default")
      (node (ref "U6") (pin "66") (pinfunction "PD2_66") (pintype "passive"))
    )
    (net (code "28") (name "/INT09") (class "Default")
      (node (ref "U6") (pin "7") (pinfunction "PU6_7") (pintype "passive"))
    )
    (net (code "29") (name "/INT13") (class "Default")
      (node (ref "U6") (pin "6") (pinfunction "PU5_6") (pintype "passive"))
    )
    (net (code "30") (name "/INT17a") (class "Default")
      (node (ref "U6") (pin "65") (pinfunction "PD1_65") (pintype "passive"))
    )
    (net (code "31") (name "/LED1") (class "Default")
      (node (ref "U6") (pin "56") (pinfunction "PB2_56") (pintype "passive"))
    )
    (net (code "32") (name "/LED2") (class "Default")
      (node (ref "U6") (pin "57") (pinfunction "PB3_57") (pintype "passive"))
    )
    (net (code "33") (name "/LED3") (class "Default")
      (node (ref "U6") (pin "59") (pinfunction "PB5_59") (pintype "passive"))
    )
    (net (code "34") (name "/LED4") (class "Default")
      (node (ref "U6") (pin "60") (pinfunction "PB6_60") (pintype "passive"))
    )
    (net (code "35") (name "/LED5") (class "Default")
      (node (ref "U6") (pin "61") (pinfunction "PN7_61") (pintype "passive"))
    )
    (net (code "36") (name "/LED_PG0") (class "Default")
      (node (ref "U6") (pin "70") (pinfunction "PG0_70") (pintype "passive"))
    )
    (net (code "37") (name "/LED_PJ4") (class "Default")
      (node (ref "U6") (pin "41") (pinfunction "PJ4_41") (pintype "passive"))
    )
    (net (code "38") (name "/LED_PJ5") (class "Default")
      (node (ref "U6") (pin "40") (pinfunction "PJ5_40") (pintype "passive"))
    )
    (net (code "39") (name "/OE_BME") (class "Default")
      (node (ref "U6") (pin "81") (pinfunction "PE4_81") (pintype "passive"))
    )
    (net (code "40") (name "/OVV1") (class "Default")
      (node (ref "U6") (pin "84") (pinfunction "PE7_84") (pintype "passive"))
    )
    (net (code "41") (name "/PMD0_DBUG") (class "Default")
      (node (ref "U6") (pin "48") (pinfunction "PC2_48") (pintype "passive"))
    )
    (net (code "42") (name "/PWM1") (class "Default")
      (node (ref "R6") (pin "1") (pinfunction "1_1") (pintype "passive"))
      (node (ref "U6") (pin "1") (pinfunction "PU0_1") (pintype "passive"))
    )
    (net (code "43") (name "/PWM2") (class "Default")
      (node (ref "U6") (pin "3") (pinfunction "PU2_3") (pintype "passive"))
    )
    (net (code "44") (name "/PWM3") (class "Default")
      (node (ref "U6") (pin "5") (pinfunction "PU4_5") (pintype "passive"))
    )
    (net (code "45") (name "/PWM_Out") (class "Default")
      (node (ref "R8") (pin "2") (pinfunction "2_2") (pintype "passive"))
      (node (ref "U3") (pin "1") (pinfunction "OUT1_1") (pintype "passive"))
    )
    (net (code "46") (name "/REGOUT1") (class "Default")
      (node (ref "C26") (pin "1") (pinfunction "1_1") (pintype "passive"))
      (node (ref "U6") (pin "87") (pinfunction "REGOUT1_87") (pintype "passive"))
    )
    (net (code "47") (name "/REGOUT2") (class "Default")
      (node (ref "C25") (pin "1") (pinfunction "1_1") (pintype "passive"))
      (node (ref "U6") (pin "86") (pinfunction "REGOUT2_86") (pintype "passive"))
    )
    (net (code "48") (name "/RESET#") (class "Default")
      (node (ref "C41") (pin "1") (pinfunction "1_1") (pintype "passive"))
      (node (ref "J8") (pin "10") (pinfunction "10_10") (pintype "passive"))
      (node (ref "R39") (pin "1") (pinfunction "1_1") (pintype "passive"))
      (node (ref "U6") (pin "92") (pinfunction "RESET_N_92") (pintype "passive"))
    )
    (net (code "49") (name "/RX_OJ") (class "Default")
      (node (ref "D6") (pin "1") (pinfunction "C_1") (pintype "passive"))
      (node (ref "U4") (pin "54") (pinfunction "BCBUS3_54") (pintype "bidirectional"))
    )
    (net (code "50") (name "/T32A01INA1") (class "Default")
      (node (ref "U6") (pin "95") (pinfunction "PF5_95") (pintype "passive"))
    )
    (net (code "51") (name "/T32A01INB0") (class "Default")
      (node (ref "U6") (pin "94") (pinfunction "PF6_94") (pintype "passive"))
    )
    (net (code "52") (name "/T32A01INB1") (class "Default")
      (node (ref "U6") (pin "93") (pinfunction "PF7_93") (pintype "passive"))
    )
    (net (code "53") (name "/TCK {slash} SWCLK") (class "Default")
      (node (ref "J8") (pin "4") (pinfunction "4_4") (pintype "passive"))
      (node (ref "R34") (pin "2") (pinfunction "2_2") (pintype "passive"))
      (node (ref "U6") (pin "99") (pinfunction "PF1_99") (pintype "passive"))
      (node (ref "U9") (pin "12") (pinfunction "B4_12") (pintype "input"))
    )
    (net (code "54") (name "/TDI {slash} JTDI") (class "Default")
      (node (ref "J8") (pin "8") (pinfunction "8_8") (pintype "passive"))
      (node (ref "R30") (pin "1") (pinfunction "1_1") (pintype "passive"))
      (node (ref "U6") (pin "97") (pinfunction "PF3_97") (pintype "passive"))
      (node (ref "U9") (pin "13") (pinfunction "B3_13") (pintype "input"))
    )
    (net (code "55") (name "/TDO {slash} SWO") (class "Default")
      (node (ref "J8") (pin "6") (pinfunction "6_6") (pintype "passive"))
      (node (ref "R31") (pin "1") (pinfunction "1_1") (pintype "passive"))
      (node (ref "U6") (pin "98") (pinfunction "PF2_98") (pintype "passive"))
      (node (ref "U9") (pin "14") (pinfunction "B2_14") (pintype "input"))
    )
    (net (code "56") (name "/TMS {slash} SWDIO") (class "Default")
      (node (ref "J8") (pin "2") (pinfunction "2_2") (pintype "passive"))
      (node (ref "R32") (pin "1") (pinfunction "1_1") (pintype "passive"))
      (node (ref "U6") (pin "100") (pinfunction "PF0_100") (pintype "passive"))
      (node (ref "U9") (pin "16") (pinfunction "B1_16") (pintype "input"))
    )
    (net (code "57") (name "/TSPI0CS1") (class "Default")
      (node (ref "U6") (pin "52") (pinfunction "PC6_52") (pintype "passive"))
    )
    (net (code "58") (name "/TSPI0RXD") (class "Default")
      (node (ref "U6") (pin "49") (pinfunction "PC3_49") (pintype "passive"))
    )
    (net (code "59") (name "/TSPI0SCK") (class "Default")
      (node (ref "U6") (pin "51") (pinfunction "PC5_51") (pintype "passive"))
    )
    (net (code "60") (name "/TSPI0TXD") (class "Default")
      (node (ref "U6") (pin "50") (pinfunction "PC4_50") (pintype "passive"))
    )
    (net (code "61") (name "/TSPI1CS0") (class "Default")
      (node (ref "R35") (pin "1") (pinfunction "1_1") (pintype "passive"))
      (node (ref "U6") (pin "72") (pinfunction "PG2_72") (pintype "passive"))
    )
    (net (code "62") (name "/TSPI1CS1") (class "Default")
      (node (ref "U6") (pin "71") (pinfunction "PG1_71") (pintype "passive"))
    )
    (net (code "63") (name "/TSPI1CSIN") (class "Default")
      (node (ref "U6") (pin "73") (pinfunction "PG3_73") (pintype "passive"))
    )
    (net (code "64") (name "/TSPI1MISO") (class "Default")
      (node (ref "U6") (pin "74") (pinfunction "PG4_74") (pintype "passive"))
    )
    (net (code "65") (name "/TSPI1MOSI") (class "Default")
      (node (ref "U6") (pin "75") (pinfunction "PG5_75") (pintype "passive"))
    )
    (net (code "66") (name "/TSPI1SCK") (class "Default")
      (node (ref "U6") (pin "76") (pinfunction "PG6_76") (pintype "passive"))
    )
    (net (code "67") (name "/TX_GREEN") (class "Default")
      (node (ref "D7") (pin "1") (pinfunction "C_1") (pintype "passive"))
      (node (ref "U4") (pin "55") (pinfunction "BCBUS4_55") (pintype "bidirectional"))
    )
    (net (code "68") (name "/USB_IC_N") (class "Default")
      (node (ref "R9") (pin "2") (pinfunction "2_2") (pintype "passive"))
      (node (ref "U4") (pin "7") (pinfunction "DM_7") (pintype "input"))
    )
    (net (code "69") (name "/USB_IC_P") (class "Default")
      (node (ref "R10") (pin "2") (pinfunction "2_2") (pintype "passive"))
      (node (ref "U4") (pin "8") (pinfunction "DP_8") (pintype "input"))
    )
    (net (code "70") (name "/USB_N") (class "Default")
      (node (ref "D3") (pin "2") (pinfunction "2_2") (pintype "passive"))
      (node (ref "J2") (pin "A7") (pinfunction "DN1_A7") (pintype "bidirectional"))
      (node (ref "J2") (pin "B7") (pinfunction "DN2_B7") (pintype "bidirectional"))
      (node (ref "R9") (pin "1") (pinfunction "1_1") (pintype "passive"))
    )
    (net (code "71") (name "/USB_P") (class "Default")
      (node (ref "D2") (pin "2") (pinfunction "2_2") (pintype "passive"))
      (node (ref "J2") (pin "A6") (pinfunction "DP1_A6") (pintype "bidirectional"))
      (node (ref "J2") (pin "B6") (pinfunction "DP2_B6") (pintype "bidirectional"))
      (node (ref "R10") (pin "1") (pinfunction "1_1") (pintype "passive"))
    )
    (net (code "72") (name "/XO1") (class "Default")
      (node (ref "C27") (pin "1") (pinfunction "1_1") (pintype "passive"))
      (node (ref "U6") (pin "91") (pinfunction "PH1_91") (pintype "passive"))
      (node (ref "Y2") (pin "3") (pinfunction "3_3") (pintype "passive"))
    )
    (net (code "73") (name "/XO2") (class "Default")
      (node (ref "C21") (pin "1") (pinfunction "1_1") (pintype "passive"))
      (node (ref "U6") (pin "90") (pinfunction "PH0_90") (pintype "passive"))
      (node (ref "Y2") (pin "1") (pinfunction "1_1") (pintype "passive"))
    )
    (net (code "74") (name "/ZO1") (class "Default")
      (node (ref "U6") (pin "82") (pinfunction "PE5_82") (pintype "passive"))
    )
    (net (code "75") (name "/nRST") (class "Default")
      (node (ref "R33") (pin "1") (pinfunction "1_1") (pintype "passive"))
      (node (ref "U6") (pin "96") (pinfunction "PF4_96") (pintype "passive"))
    )
    (net (code "76") (name "1V8_FT") (class "Default")
      (node (ref "C22") (pin "1") (pinfunction "1_1") (pintype "passive"))
      (node (ref "C23") (pin "1") (pinfunction "1_1") (pintype "passive"))
      (node (ref "C24") (pin "1") (pinfunction "1_1") (pintype "passive"))
      (node (ref "C4") (pin "1") (pinfunction "1_1") (pintype "passive"))
      (node (ref "U4") (pin "12") (pinfunction "VCORE_12") (pintype "power_in"))
      (node (ref "U4") (pin "37") (pinfunction "VCORE_37") (pintype "power_in"))
      (node (ref "U4") (pin "49") (pinfunction "VREGOUT_49") (pintype "power_in"))
      (node (ref "U4") (pin "64") (pinfunction "VCORE_64") (pintype "power_in"))
    )
    (net (code "77") (name "3V3_FT") (class "Default")
      (node (ref "C14") (pin "1") (pinfunction "1_1") (pintype "passive"))
      (node (ref "C15") (pin "1") (pinfunction "1_1") (pintype "passive"))
      (node (ref "C16") (pin "1") (pinfunction "1_1") (pintype "passive"))
      (node (ref "C17") (pin "1") (pinfunction "1_1") (pintype "passive"))
      (node (ref "C3") (pin "1") (pinfunction "1_1") (pintype "passive"))
      (node (ref "C37") (pin "1") (pinfunction "1_1") (pintype "passive"))
      (node (ref "C38") (pin "1") (pinfunction "1_1") (pintype "passive"))
      (node (ref "C42") (pin "1") (pinfunction "1_1") (pintype "passive"))
      (node (ref "C5") (pin "1") (pinfunction "1_1") (pintype "passive"))
      (node (ref "C6") (pin "1") (pinfunction "1_1") (pintype "passive"))
      (node (ref "FB1") (pin "1") (pinfunction "1_1") (pintype "passive"))
      (node (ref "FB2") (pin "1") (pinfunction "1_1") (pintype "passive"))
      (node (ref "R11") (pin "1") (pinfunction "1_1") (pintype "passive"))
      (node (ref "R13") (pin "2") (pinfunction "2_2") (pintype "passive"))
      (node (ref "R14") (pin "2") (pinfunction "2_2") (pintype "passive"))
      (node (ref "R15") (pin "2") (pinfunction "2_2") (pintype "passive"))
      (node (ref "R16") (pin "2") (pinfunction "2_2") (pintype "passive"))
      (node (ref "R26") (pin "2") (pinfunction "2_2") (pintype "passive"))
      (node (ref "R40") (pin "2") (pinfunction "2_2") (pintype "passive"))
      (node (ref "TP1") (pin "1") (pinfunction "18_1") (pintype "passive"))
      (node (ref "U10") (pin "5") (pinfunction "VOUT_5") (pintype "passive"))
      (node (ref "U4") (pin "20") (pinfunction "VCCIO_20") (pintype "power_in"))
      (node (ref "U4") (pin "31") (pinfunction "VCCIO_31") (pintype "power_in"))
      (node (ref "U4") (pin "42") (pinfunction "VCCIO_42") (pintype "power_in"))
      (node (ref "U4") (pin "50") (pinfunction "VREGIN_50") (pintype "power_in"))
      (node (ref "U4") (pin "56") (pinfunction "VCCIO_56") (pintype "power_in"))
      (node (ref "U5") (pin "6") (pinfunction "VCC_6") (pintype "power_in"))
      (node (ref "U7") (pin "1") (pinfunction "VCCA_1") (pintype "power_in"))
      (node (ref "U8") (pin "5") (pinfunction "OE_5") (pintype "input"))
      (node (ref "U8") (pin "6") (pinfunction "VCCB_6") (pintype "power_in"))
      (node (ref "U9") (pin "2") (pinfunction "VCCA_2") (pintype "input"))
    )
    (net (code "78") (name "5V") (class "Default")
      (node (ref "C13") (pin "1") (pinfunction "1_1") (pintype "passive"))
      (node (ref "C30") (pin "1") (pinfunction "1_1") (pintype "passive"))
      (node (ref "C31") (pin "1") (pinfunction "1_1") (pintype "passive"))
      (node (ref "C39") (pin "1") (pinfunction "1_1") (pintype "passive"))
      (node (ref "C40") (pin "1") (pinfunction "1_1") (pintype "passive"))
      (node (ref "C43") (pin "1") (pinfunction "1_1") (pintype "passive"))
      (node (ref "D4") (pin "1") (pinfunction "C_1") (pintype "passive"))
      (node (ref "FB3") (pin "1") (pinfunction "1_1") (pintype "passive"))
      (node (ref "J8") (pin "1") (pinfunction "1_1") (pintype "passive"))
      (node (ref "R30") (pin "2") (pinfunction "2_2") (pintype "passive"))
      (node (ref "R31") (pin "2") (pinfunction "2_2") (pintype "passive"))
      (node (ref "R32") (pin "2") (pinfunction "2_2") (pintype "passive"))
      (node (ref "R33") (pin "2") (pinfunction "2_2") (pintype "passive"))
      (node (ref "R35") (pin "2") (pinfunction "2_2") (pintype "passive"))
      (node (ref "R36") (pin "2") (pinfunction "2_2") (pintype "passive"))
      (node (ref "R37") (pin "2") (pinfunction "2_2") (pintype "passive"))
      (node (ref "R38") (pin "2") (pinfunction "2_2") (pintype "passive"))
      (node (ref "TP2") (pin "1") (pinfunction "18_1") (pintype "passive"))
      (node (ref "U10") (pin "1") (pinfunction "VIN_1") (pintype "passive"))
      (node (ref "U10") (pin "3") (pinfunction "CONTROL_3") (pintype "passive"))
      (node (ref "U6") (pin "63") (pinfunction "DVDD5A_63") (pintype "passive"))
      (node (ref "U6") (pin "85") (pinfunction "DVDD5B_85") (pintype "passive"))
      (node (ref "U7") (pin "5") (pinfunction "OE_5") (pintype "input"))
      (node (ref "U7") (pin "6") (pinfunction "VCCB_6") (pintype "power_in"))
      (node (ref "U8") (pin "1") (pinfunction "VCCA_1") (pintype "power_in"))
      (node (ref "U9") (pin "15") (pinfunction "VCBB_15") (pintype "input"))
    )
    (net (code "79") (name "5V_T") (class "Default")
      (node (ref "C34") (pin "1") (pinfunction "1_1") (pintype "passive"))
      (node (ref "C35") (pin "1") (pinfunction "1_1") (pintype "passive"))
      (node (ref "C36") (pin "1") (pinfunction "1_1") (pintype "passive"))
      (node (ref "FB3") (pin "2") (pinfunction "2_2") (pintype "passive"))
      (node (ref "U6") (pin "33") (pinfunction "AVDD5_33") (pintype "passive"))
      (node (ref "U6") (pin "34") (pinfunction "VREFH_34") (pintype "passive"))
    )
    (net (code "80") (name "10V") (class "Default")
      (node (ref "C1") (pin "1") (pinfunction "1_1") (pintype "passive"))
      (node (ref "U3") (pin "8") (pinfunction "v+_8") (pintype "power_in"))
    )
    (net (code "81") (name "GND") (class "Default")
      (node (ref "C1") (pin "2") (pinfunction "2_2") (pintype "passive"))
      (node (ref "C13") (pin "2") (pinfunction "2_2") (pintype "passive"))
      (node (ref "C14") (pin "2") (pinfunction "2_2") (pintype "passive"))
      (node (ref "C15") (pin "2") (pinfunction "2_2") (pintype "passive"))
      (node (ref "C16") (pin "2") (pinfunction "2_2") (pintype "passive"))
      (node (ref "C17") (pin "2") (pinfunction "2_2") (pintype "passive"))
      (node (ref "C18") (pin "2") (pinfunction "2_2") (pintype "passive"))
      (node (ref "C19") (pin "2") (pinfunction "2_2") (pintype "passive"))
      (node (ref "C2") (pin "1") (pinfunction "1_1") (pintype "passive"))
      (node (ref "C21") (pin "2") (pinfunction "2_2") (pintype "passive"))
      (node (ref "C22") (pin "2") (pinfunction "2_2") (pintype "passive"))
      (node (ref "C23") (pin "2") (pinfunction "2_2") (pintype "passive"))
      (node (ref "C24") (pin "2") (pinfunction "2_2") (pintype "passive"))
      (node (ref "C25") (pin "2") (pinfunction "2_2") (pintype "passive"))
      (node (ref "C26") (pin "2") (pinfunction "2_2") (pintype "passive"))
      (node (ref "C27") (pin "2") (pinfunction "2_2") (pintype "passive"))
      (node (ref "C28") (pin "2") (pinfunction "2_2") (pintype "passive"))
      (node (ref "C29") (pin "2") (pinfunction "2_2") (pintype "passive"))
      (node (ref "C3") (pin "2") (pinfunction "2_2") (pintype "passive"))
      (node (ref "C30") (pin "2") (pinfunction "2_2") (pintype "passive"))
      (node (ref "C31") (pin "2") (pinfunction "2_2") (pintype "passive"))
      (node (ref "C32") (pin "2") (pinfunction "2_2") (pintype "passive"))
      (node (ref "C33") (pin "2") (pinfunction "2_2") (pintype "passive"))
      (node (ref "C34") (pin "2") (pinfunction "2_2") (pintype "passive"))
      (node (ref "C35") (pin "2") (pinfunction "2_2") (pintype "passive"))
      (node (ref "C36") (pin "2") (pinfunction "2_2") (pintype "passive"))
      (node (ref "C37") (pin "2") (pinfunction "2_2") (pintype "passive"))
      (node (ref "C38") (pin "2") (pinfunction "2_2") (pintype "passive"))
      (node (ref "C39") (pin "2") (pinfunction "2_2") (pintype "passive"))
      (node (ref "C4") (pin "2") (pinfunction "2_2") (pintype "passive"))
      (node (ref "C40") (pin "2") (pinfunction "2_2") (pintype "passive"))
      (node (ref "C41") (pin "2") (pinfunction "2_2") (pintype "passive"))
      (node (ref "C42") (pin "2") (pinfunction "2_2") (pintype "passive"))
      (node (ref "C43") (pin "2") (pinfunction "2_2") (pintype "passive"))
      (node (ref "C5") (pin "2") (pinfunction "2_2") (pintype "passive"))
      (node (ref "C6") (pin "2") (pinfunction "2_2") (pintype "passive"))
      (node (ref "D2") (pin "1") (pinfunction "1_1") (pintype "passive"))
      (node (ref "D3") (pin "1") (pinfunction "1_1") (pintype "passive"))
      (node (ref "J2") (pin "A1B12") (pinfunction "GND1_A1B12") (pintype "power_in"))
      (node (ref "J2") (pin "B1A12") (pinfunction "GND2_B1A12") (pintype "power_in"))
      (node (ref "J2") (pin "SH1") (pinfunction "SHIELD1_SH1") (pintype "passive"))
      (node (ref "J2") (pin "SH2") (pinfunction "SHIELD2_SH2") (pintype "passive"))
      (node (ref "J2") (pin "SH3") (pinfunction "SHIELD3_SH3") (pintype "passive"))
      (node (ref "J2") (pin "SH4") (pinfunction "SHIELD4_SH4") (pintype "passive"))
      (node (ref "J8") (pin "3") (pinfunction "3_3") (pintype "passive"))
      (node (ref "J8") (pin "5") (pinfunction "5_5") (pintype "passive"))
      (node (ref "J8") (pin "9") (pinfunction "9_9") (pintype "passive"))
      (node (ref "R12") (pin "1") (pinfunction "1_1") (pintype "passive"))
      (node (ref "R24") (pin "2") (pinfunction "2_2") (pintype "passive"))
      (node (ref "R25") (pin "2") (pinfunction "2_2") (pintype "passive"))
      (node (ref "R28") (pin "1") (pinfunction "1_1") (pintype "passive"))
      (node (ref "R29") (pin "1") (pinfunction "1_1") (pintype "passive"))
      (node (ref "R34") (pin "1") (pinfunction "1_1") (pintype "passive"))
      (node (ref "R41") (pin "1") (pinfunction "1_1") (pintype "passive"))
      (node (ref "R7") (pin "1") (pinfunction "1_1") (pintype "passive"))
      (node (ref "SW1") (pin "1") (pinfunction "1_1") (pintype "passive"))
      (node (ref "SW1") (pin "2") (pinfunction "2_2") (pintype "passive"))
      (node (ref "U10") (pin "2") (pinfunction "GND_2") (pintype "passive"))
      (node (ref "U3") (pin "4") (pinfunction "V-_4") (pintype "power_in"))
      (node (ref "U4") (pin "1") (pinfunction "GND_1") (pintype "power_in"))
      (node (ref "U4") (pin "10") (pinfunction "AGND_10") (pintype "power_in"))
      (node (ref "U4") (pin "11") (pinfunction "GND_11") (pintype "power_in"))
      (node (ref "U4") (pin "13") (pinfunction "TEST_13") (pintype "input"))
      (node (ref "U4") (pin "15") (pinfunction "GND_15") (pintype "power_in"))
      (node (ref "U4") (pin "25") (pinfunction "GND_25") (pintype "power_in"))
      (node (ref "U4") (pin "35") (pinfunction "GND_35") (pintype "power_in"))
      (node (ref "U4") (pin "47") (pinfunction "GND_47") (pintype "power_in"))
      (node (ref "U4") (pin "5") (pinfunction "GND_5") (pintype "power_in"))
      (node (ref "U4") (pin "51") (pinfunction "GND_51") (pintype "power_in"))
      (node (ref "U5") (pin "2") (pinfunction "VSS_2") (pintype "power_in"))
      (node (ref "U6") (pin "14") (pinfunction "DVSSC_14") (pintype "passive"))
      (node (ref "U7") (pin "2") (pinfunction "GND_2") (pintype "power_in"))
      (node (ref "U8") (pin "2") (pinfunction "GND_2") (pintype "power_in"))
      (node (ref "U9") (pin "10") (pinfunction "B6_10") (pintype "input"))
      (node (ref "U9") (pin "11") (pinfunction "B5_11") (pintype "input"))
      (node (ref "U9") (pin "6") (pinfunction "A5_6") (pintype "input"))
      (node (ref "U9") (pin "7") (pinfunction "A6_7") (pintype "input"))
      (node (ref "U9") (pin "9") (pinfunction "GND_9") (pintype "input"))
    )
    (net (code "82") (name "MCU_RX") (class "Default")
      (node (ref "U6") (pin "10") (pinfunction "PN1_10") (pintype "passive"))
      (node (ref "U7") (pin "4") (pinfunction "BY_4") (pintype "output"))
    )
    (net (code "83") (name "MCU_TX") (class "Default")
      (node (ref "U6") (pin "9") (pinfunction "PN0_9") (pintype "passive"))
      (node (ref "U8") (pin "3") (pinfunction "A_3") (pintype "input"))
    )
    (net (code "84") (name "Net-(D6-A)") (class "Default")
      (node (ref "D6") (pin "2") (pinfunction "A_2") (pintype "passive"))
      (node (ref "R14") (pin "1") (pinfunction "1_1") (pintype "passive"))
    )
    (net (code "85") (name "Net-(D7-A)") (class "Default")
      (node (ref "D7") (pin "2") (pinfunction "A_2") (pintype "passive"))
      (node (ref "R15") (pin "1") (pinfunction "1_1") (pintype "passive"))
    )
    (net (code "86") (name "Net-(R38-Pad1)") (class "Default")
      (node (ref "R38") (pin "1") (pinfunction "1_1") (pintype "passive"))
      (node (ref "R39") (pin "2") (pinfunction "2_2") (pintype "passive"))
      (node (ref "SW1") (pin "3") (pinfunction "3_3") (pintype "passive"))
      (node (ref "SW1") (pin "4") (pinfunction "4_4") (pintype "passive"))
    )
    (net (code "87") (name "Net-(U3A-IN1+)") (class "Default")
      (node (ref "C2") (pin "2") (pinfunction "2_2") (pintype "passive"))
      (node (ref "R6") (pin "2") (pinfunction "2_2") (pintype "passive"))
      (node (ref "U3") (pin "3") (pinfunction "IN1+_3") (pintype "tri_state"))
    )
    (net (code "88") (name "Net-(U3A-IN1-)") (class "Default")
      (node (ref "R7") (pin "2") (pinfunction "2_2") (pintype "passive"))
      (node (ref "R8") (pin "1") (pinfunction "1_1") (pintype "passive"))
      (node (ref "U3") (pin "2") (pinfunction "IN1-_2") (pintype "tri_state"))
    )
    (net (code "89") (name "Net-(U4-OSCI)") (class "Default")
      (node (ref "C19") (pin "1") (pinfunction "1_1") (pintype "passive"))
      (node (ref "U4") (pin "2") (pinfunction "OSCI_2") (pintype "input"))
      (node (ref "Y1") (pin "1") (pinfunction "1_1") (pintype "passive"))
    )
    (net (code "90") (name "Net-(U4-OSCO)") (class "Default")
      (node (ref "C18") (pin "1") (pinfunction "1_1") (pintype "passive"))
      (node (ref "U4") (pin "3") (pinfunction "OSCO_3") (pintype "output"))
      (node (ref "Y1") (pin "3") (pinfunction "3_3") (pintype "passive"))
    )
    (net (code "91") (name "Net-(U4-PWREN#)") (class "Default")
      (node (ref "R29") (pin "2") (pinfunction "2_2") (pintype "passive"))
      (node (ref "U4") (pin "60") (pinfunction "PWREN#_60") (pintype "output"))
    )
    (net (code "92") (name "Net-(U4-REF)") (class "Default")
      (node (ref "R12") (pin "2") (pinfunction "2_2") (pintype "passive"))
      (node (ref "U4") (pin "6") (pinfunction "REF_6") (pintype "input"))
    )
    (net (code "93") (name "Net-(U4-RESET#)") (class "Default")
      (node (ref "R11") (pin "2") (pinfunction "2_2") (pintype "passive"))
      (node (ref "U4") (pin "14") (pinfunction "RESET#_14") (pintype "input"))
    )
    (net (code "94") (name "Net-(U4-SUSPEND#)") (class "Default")
      (node (ref "R28") (pin "2") (pinfunction "2_2") (pintype "passive"))
      (node (ref "U4") (pin "36") (pinfunction "SUSPEND#_36") (pintype "output"))
    )
    (net (code "95") (name "Net-(U5-DO)") (class "Default")
      (node (ref "R13") (pin "1") (pinfunction "1_1") (pintype "passive"))
      (node (ref "R27") (pin "1") (pinfunction "1_1") (pintype "passive"))
      (node (ref "U5") (pin "1") (pinfunction "DO_1") (pintype "tri_state"))
    )
    (net (code "96") (name "TCK") (class "Default")
      (node (ref "R40") (pin "1") (pinfunction "1_1") (pintype "passive"))
      (node (ref "R41") (pin "2") (pinfunction "2_2") (pintype "passive"))
      (node (ref "U4") (pin "16") (pinfunction "ADBUS0_16") (pintype "bidirectional"))
      (node (ref "U9") (pin "5") (pinfunction "A4_5") (pintype "input"))
      (node (ref "U9") (pin "8") (pinfunction "OE_8") (pintype "input"))
    )
    (net (code "97") (name "TDI") (class "Default")
      (node (ref "U4") (pin "17") (pinfunction "ADBUS1_17") (pintype "bidirectional"))
      (node (ref "U9") (pin "4") (pinfunction "A3_4") (pintype "input"))
    )
    (net (code "98") (name "TDO") (class "Default")
      (node (ref "U4") (pin "18") (pinfunction "ADBUS2_18") (pintype "bidirectional"))
      (node (ref "U9") (pin "3") (pinfunction "A2_3") (pintype "input"))
    )
    (net (code "99") (name "TMS") (class "Default")
      (node (ref "U4") (pin "19") (pinfunction "ADBUS3_19") (pintype "bidirectional"))
      (node (ref "U9") (pin "1") (pinfunction "A1_1") (pintype "input"))
    )
    (net (code "100") (name "USB_RX") (class "Default")
      (node (ref "U4") (pin "39") (pinfunction "BDBUS1_39") (pintype "bidirectional"))
      (node (ref "U8") (pin "4") (pinfunction "BY_4") (pintype "output"))
    )
    (net (code "101") (name "USB_TX") (class "Default")
      (node (ref "U4") (pin "38") (pinfunction "BDBUS0_38") (pintype "bidirectional"))
      (node (ref "U7") (pin "3") (pinfunction "A_3") (pintype "input"))
    )
    (net (code "102") (name "VBUS") (class "Default")
      (node (ref "D4") (pin "2") (pinfunction "A_2") (pintype "passive"))
      (node (ref "J2") (pin "A4B9") (pinfunction "VBUS1_A4B9") (pintype "power_in"))
      (node (ref "J2") (pin "B4A9") (pinfunction "VBUS2_B4A9") (pintype "power_in"))
    )
    (net (code "103") (name "VPHY") (class "Default")
      (node (ref "C28") (pin "1") (pinfunction "1_1") (pintype "passive"))
      (node (ref "C29") (pin "1") (pinfunction "1_1") (pintype "passive"))
      (node (ref "FB1") (pin "2") (pinfunction "2_2") (pintype "passive"))
      (node (ref "U4") (pin "4") (pinfunction "VPHY_4") (pintype "power_in"))
    )
    (net (code "104") (name "VPLL") (class "Default")
      (node (ref "C32") (pin "1") (pinfunction "1_1") (pintype "passive"))
      (node (ref "C33") (pin "1") (pinfunction "1_1") (pintype "passive"))
      (node (ref "FB2") (pin "2") (pinfunction "2_2") (pintype "passive"))
      (node (ref "U4") (pin "9") (pinfunction "VPLL_9") (pintype "power_in"))
    )
    (net (code "105") (name "unconnected-(J2-SBU1-PadA8)") (class "Default")
      (node (ref "J2") (pin "A8") (pinfunction "SBU1_A8") (pintype "bidirectional+no_connect"))
    )
    (net (code "106") (name "unconnected-(J2-SBU2-PadB8)") (class "Default")
      (node (ref "J2") (pin "B8") (pinfunction "SBU2_B8") (pintype "bidirectional+no_connect"))
    )
    (net (code "107") (name "unconnected-(J8-Pad7)") (class "Default")
      (node (ref "J8") (pin "7") (pinfunction "7_7") (pintype "passive+no_connect"))
    )
    (net (code "108") (name "unconnected-(U4-ACBUS0-Pad26)") (class "Default")
      (node (ref "U4") (pin "26") (pinfunction "ACBUS0_26") (pintype "bidirectional"))
    )
    (net (code "109") (name "unconnected-(U4-ACBUS1-Pad27)") (class "Default")
      (node (ref "U4") (pin "27") (pinfunction "ACBUS1_27") (pintype "bidirectional"))
    )
    (net (code "110") (name "unconnected-(U4-ACBUS2-Pad28)") (class "Default")
      (node (ref "U4") (pin "28") (pinfunction "ACBUS2_28") (pintype "bidirectional"))
    )
    (net (code "111") (name "unconnected-(U4-ACBUS3-Pad29)") (class "Default")
      (node (ref "U4") (pin "29") (pinfunction "ACBUS3_29") (pintype "bidirectional"))
    )
    (net (code "112") (name "unconnected-(U4-ACBUS4-Pad30)") (class "Default")
      (node (ref "U4") (pin "30") (pinfunction "ACBUS4_30") (pintype "bidirectional"))
    )
    (net (code "113") (name "unconnected-(U4-ACBUS5-Pad32)") (class "Default")
      (node (ref "U4") (pin "32") (pinfunction "ACBUS5_32") (pintype "bidirectional"))
    )
    (net (code "114") (name "unconnected-(U4-ACBUS6-Pad33)") (class "Default")
      (node (ref "U4") (pin "33") (pinfunction "ACBUS6_33") (pintype "bidirectional"))
    )
    (net (code "115") (name "unconnected-(U4-ACBUS7-Pad34)") (class "Default")
      (node (ref "U4") (pin "34") (pinfunction "ACBUS7_34") (pintype "bidirectional"))
    )
    (net (code "116") (name "unconnected-(U4-ADBUS4-Pad21)") (class "Default")
      (node (ref "U4") (pin "21") (pinfunction "ADBUS4_21") (pintype "bidirectional"))
    )
    (net (code "117") (name "unconnected-(U4-ADBUS5-Pad22)") (class "Default")
      (node (ref "U4") (pin "22") (pinfunction "ADBUS5_22") (pintype "bidirectional"))
    )
    (net (code "118") (name "unconnected-(U4-ADBUS6-Pad23)") (class "Default")
      (node (ref "U4") (pin "23") (pinfunction "ADBUS6_23") (pintype "bidirectional"))
    )
    (net (code "119") (name "unconnected-(U4-ADBUS7-Pad24)") (class "Default")
      (node (ref "U4") (pin "24") (pinfunction "ADBUS7_24") (pintype "bidirectional"))
    )
    (net (code "120") (name "unconnected-(U4-BCBUS0-Pad48)") (class "Default")
      (node (ref "U4") (pin "48") (pinfunction "BCBUS0_48") (pintype "bidirectional"))
    )
    (net (code "121") (name "unconnected-(U4-BCBUS1-Pad52)") (class "Default")
      (node (ref "U4") (pin "52") (pinfunction "BCBUS1_52") (pintype "bidirectional"))
    )
    (net (code "122") (name "unconnected-(U4-BCBUS2-Pad53)") (class "Default")
      (node (ref "U4") (pin "53") (pinfunction "BCBUS2_53") (pintype "bidirectional"))
    )
    (net (code "123") (name "unconnected-(U4-BCBUS5-Pad57)") (class "Default")
      (node (ref "U4") (pin "57") (pinfunction "BCBUS5_57") (pintype "bidirectional"))
    )
    (net (code "124") (name "unconnected-(U4-BCBUS6-Pad58)") (class "Default")
      (node (ref "U4") (pin "58") (pinfunction "BCBUS6_58") (pintype "bidirectional"))
    )
    (net (code "125") (name "unconnected-(U4-BDBUS2-Pad40)") (class "Default")
      (node (ref "U4") (pin "40") (pinfunction "BDBUS2_40") (pintype "bidirectional"))
    )
    (net (code "126") (name "unconnected-(U4-BDBUS3-Pad41)") (class "Default")
      (node (ref "U4") (pin "41") (pinfunction "BDBUS3_41") (pintype "bidirectional"))
    )
    (net (code "127") (name "unconnected-(U4-BDBUS4-Pad43)") (class "Default")
      (node (ref "U4") (pin "43") (pinfunction "BDBUS4_43") (pintype "bidirectional"))
    )
    (net (code "128") (name "unconnected-(U4-BDBUS5-Pad44)") (class "Default")
      (node (ref "U4") (pin "44") (pinfunction "BDBUS5_44") (pintype "bidirectional"))
    )
    (net (code "129") (name "unconnected-(U4-BDBUS6-Pad45)") (class "Default")
      (node (ref "U4") (pin "45") (pinfunction "BDBUS6_45") (pintype "bidirectional"))
    )
    (net (code "130") (name "unconnected-(U4-BDBUS7-Pad46)") (class "Default")
      (node (ref "U4") (pin "46") (pinfunction "BDBUS7_46") (pintype "bidirectional"))
    )
    (net (code "131") (name "unconnected-(U6-PA0-Pad15)") (class "Default")
      (node (ref "U6") (pin "15") (pinfunction "PA0_15") (pintype "passive"))
    )
    (net (code "132") (name "unconnected-(U6-PA1-Pad16)") (class "Default")
      (node (ref "U6") (pin "16") (pinfunction "PA1_16") (pintype "passive"))
    )
    (net (code "133") (name "unconnected-(U6-PA2-Pad17)") (class "Default")
      (node (ref "U6") (pin "17") (pinfunction "PA2_17") (pintype "passive"))
    )
    (net (code "134") (name "unconnected-(U6-PA3-Pad18)") (class "Default")
      (node (ref "U6") (pin "18") (pinfunction "PA3_18") (pintype "passive"))
    )
    (net (code "135") (name "unconnected-(U6-PA4-Pad19)") (class "Default")
      (node (ref "U6") (pin "19") (pinfunction "PA4_19") (pintype "passive"))
    )
    (net (code "136") (name "unconnected-(U6-PB0-Pad54)") (class "Default")
      (node (ref "U6") (pin "54") (pinfunction "PB0_54") (pintype "passive"))
    )
    (net (code "137") (name "unconnected-(U6-PB1-Pad55)") (class "Default")
      (node (ref "U6") (pin "55") (pinfunction "PB1_55") (pintype "passive"))
    )
    (net (code "138") (name "unconnected-(U6-PB4-Pad58)") (class "Default")
      (node (ref "U6") (pin "58") (pinfunction "PB4_58") (pintype "passive"))
    )
    (net (code "139") (name "unconnected-(U6-PC7-Pad53)") (class "Default")
      (node (ref "U6") (pin "53") (pinfunction "PC7_53") (pintype "passive"))
    )
    (net (code "140") (name "unconnected-(U6-PD0-Pad64)") (class "Default")
      (node (ref "U6") (pin "64") (pinfunction "PD0_64") (pintype "passive"))
    )
    (net (code "141") (name "unconnected-(U6-PD5-Pad69)") (class "Default")
      (node (ref "U6") (pin "69") (pinfunction "PD5_69") (pintype "passive"))
    )
    (net (code "142") (name "unconnected-(U6-PE0-Pad77)") (class "Default")
      (node (ref "U6") (pin "77") (pinfunction "PE0_77") (pintype "passive"))
    )
    (net (code "143") (name "unconnected-(U6-PE1-Pad78)") (class "Default")
      (node (ref "U6") (pin "78") (pinfunction "PE1_78") (pintype "passive"))
    )
    (net (code "144") (name "unconnected-(U6-PE2-Pad79)") (class "Default")
      (node (ref "U6") (pin "79") (pinfunction "PE2_79") (pintype "passive"))
    )
    (net (code "145") (name "unconnected-(U6-PE3-Pad80)") (class "Default")
      (node (ref "U6") (pin "80") (pinfunction "PE3_80") (pintype "passive"))
    )
    (net (code "146") (name "unconnected-(U6-PL0-Pad20)") (class "Default")
      (node (ref "U6") (pin "20") (pinfunction "PL0_20") (pintype "passive"))
    )
    (net (code "147") (name "unconnected-(U6-PL1-Pad21)") (class "Default")
      (node (ref "U6") (pin "21") (pinfunction "PL1_21") (pintype "passive"))
    )
    (net (code "148") (name "unconnected-(U6-PL2-Pad22)") (class "Default")
      (node (ref "U6") (pin "22") (pinfunction "PL2_22") (pintype "passive"))
    )
    (net (code "149") (name "unconnected-(U6-PL3-Pad23)") (class "Default")
      (node (ref "U6") (pin "23") (pinfunction "PL3_23") (pintype "passive"))
    )
    (net (code "150") (name "unconnected-(U6-PL4-Pad24)") (class "Default")
      (node (ref "U6") (pin "24") (pinfunction "PL4_24") (pintype "passive"))
    )
    (net (code "151") (name "unconnected-(U6-PL5-Pad25)") (class "Default")
      (node (ref "U6") (pin "25") (pinfunction "PL5_25") (pintype "passive"))
    )
    (net (code "152") (name "unconnected-(U6-PN2-Pad11)") (class "Default")
      (node (ref "U6") (pin "11") (pinfunction "PN2_11") (pintype "passive"))
    )
    (net (code "153") (name "unconnected-(U6-PU1-Pad2)") (class "Default")
      (node (ref "U6") (pin "2") (pinfunction "PU1_2") (pintype "passive"))
    )
    (net (code "154") (name "unconnected-(U6-PU3-Pad4)") (class "Default")
      (node (ref "U6") (pin "4") (pinfunction "PU3_4") (pintype "passive"))
    )
    (net (code "155") (name "unconnected-(U6-PU7-Pad8)") (class "Default")
      (node (ref "U6") (pin "8") (pinfunction "PU7_8") (pintype "passive"))
    )
    (net (code "156") (name "unconnected-(U6-PV0-Pad12)") (class "Default")
      (node (ref "U6") (pin "12") (pinfunction "PV0_12") (pintype "passive"))
    )
    (net (code "157") (name "unconnected-(U6-PV1-Pad13)") (class "Default")
      (node (ref "U6") (pin "13") (pinfunction "PV1_13") (pintype "passive"))
    )
    (net (code "158") (name "unconnected-(U10-NC-Pad4)") (class "Default")
      (node (ref "U10") (pin "4") (pinfunction "NC_4") (pintype "passive+no_connect"))
    )
    (net (code "159") (name "unconnected-(Y1-MNT_1-Pad2)") (class "Default")
      (node (ref "Y1") (pin "2") (pinfunction "MNT_1_2") (pintype "passive"))
    )
    (net (code "160") (name "unconnected-(Y1-MNT_2-Pad4)") (class "Default")
      (node (ref "Y1") (pin "4") (pinfunction "MNT_2_4") (pintype "passive"))
    )
    (net (code "161") (name "unconnected-(Y2-MNT_1-Pad2)") (class "Default")
      (node (ref "Y2") (pin "2") (pinfunction "MNT_1_2") (pintype "passive"))
    )
    (net (code "162") (name "unconnected-(Y2-MNT_2-Pad4)") (class "Default")
      (node (ref "Y2") (pin "4") (pinfunction "MNT_2_4") (pintype "passive"))
    )
  )
)
